# SNES-Adapter-Board.net
KiCad netlist of a schematic drawn in EAGLE
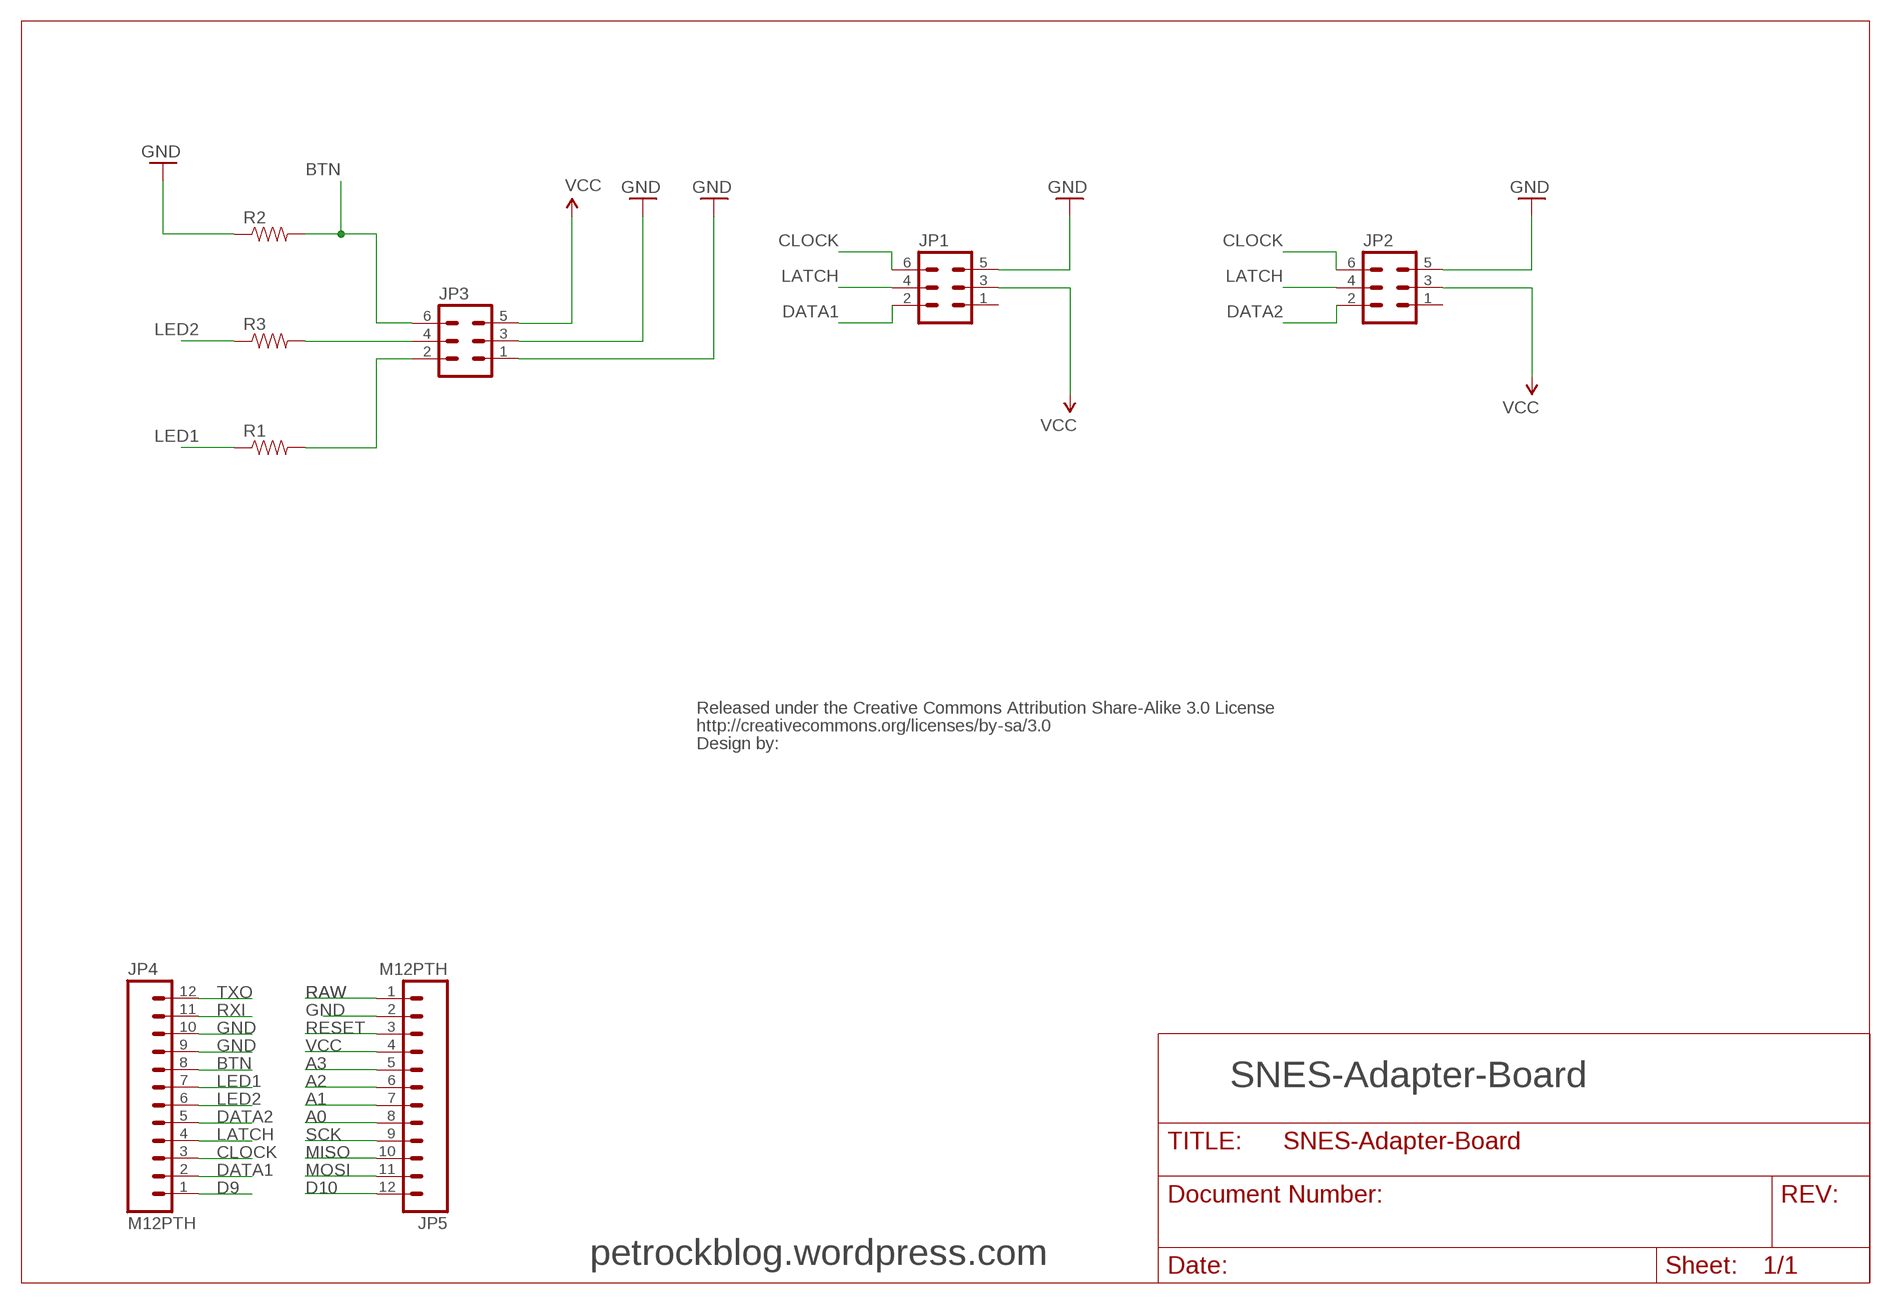
[diagram p0: schematic, sheet 1]

(export (version "E")
  (design (tool "Eeschema 10.0.6"))
  (components
    (comp (ref "JP1")
      (value "ML6")
      (footprint "eagle-import:ML6")
      (libsource (lib "eagle-import") (part "ML6"))
    )
    (comp (ref "JP2")
      (value "ML6")
      (footprint "eagle-import:ML6")
      (libsource (lib "eagle-import") (part "ML6"))
    )
    (comp (ref "JP3")
      (value "ML6")
      (footprint "eagle-import:ML6")
      (libsource (lib "eagle-import") (part "ML6"))
    )
    (comp (ref "JP4")
      (value "M12PTH")
      (footprint "eagle-import:1X12")
      (libsource (lib "eagle-import") (part "M12PTH"))
    )
    (comp (ref "JP5")
      (value "M12PTH")
      (footprint "eagle-import:1X12")
      (libsource (lib "eagle-import") (part "M12PTH"))
    )
    (comp (ref "R1")
      (value "RESISTORPTH-1/4W")
      (footprint "eagle-import:AXIAL-0.4")
      (libsource (lib "eagle-import") (part "RESISTORPTH-1/4W"))
    )
    (comp (ref "R2")
      (value "RESISTORPTH-1/4W")
      (footprint "eagle-import:AXIAL-0.4")
      (libsource (lib "eagle-import") (part "RESISTORPTH-1/4W"))
    )
    (comp (ref "R3")
      (value "RESISTORPTH-1/4W")
      (footprint "eagle-import:AXIAL-0.4")
      (libsource (lib "eagle-import") (part "RESISTORPTH-1/4W"))
    )
    (comp (ref "U$2")
      (value "CREATIVE_COMMONS")
      (footprint "eagle-import:CREATIVE_COMMONS")
      (libsource (lib "eagle-import") (part "CREATIVE_COMMONS"))
    )
  )
  (nets
    (net (code "1") (name "/A0") (class "Default")
      (node (ref "JP5") (pin "8") (pinfunction "8_8") (pintype "passive"))
    )
    (net (code "2") (name "/A1") (class "Default")
      (node (ref "JP5") (pin "7") (pinfunction "7_7") (pintype "passive"))
    )
    (net (code "3") (name "/A2") (class "Default")
      (node (ref "JP5") (pin "6") (pinfunction "6_6") (pintype "passive"))
    )
    (net (code "4") (name "/A3") (class "Default")
      (node (ref "JP5") (pin "5") (pinfunction "5_5") (pintype "passive"))
    )
    (net (code "5") (name "/BTN") (class "Default")
      (node (ref "JP3") (pin "6") (pinfunction "6_6") (pintype "passive"))
      (node (ref "JP4") (pin "8") (pinfunction "8_8") (pintype "passive"))
      (node (ref "R2") (pin "P$2") (pinfunction "2_P$2") (pintype "passive"))
    )
    (net (code "6") (name "/CLOCK") (class "Default")
      (node (ref "JP1") (pin "6") (pinfunction "6_6") (pintype "passive"))
      (node (ref "JP2") (pin "6") (pinfunction "6_6") (pintype "passive"))
      (node (ref "JP4") (pin "3") (pinfunction "3_3") (pintype "passive"))
    )
    (net (code "7") (name "/D9") (class "Default")
      (node (ref "JP4") (pin "1") (pinfunction "1_1") (pintype "passive"))
    )
    (net (code "8") (name "/D10") (class "Default")
      (node (ref "JP5") (pin "12") (pinfunction "12_12") (pintype "passive"))
    )
    (net (code "9") (name "/DATA1") (class "Default")
      (node (ref "JP1") (pin "2") (pinfunction "2_2") (pintype "passive"))
      (node (ref "JP4") (pin "2") (pinfunction "2_2") (pintype "passive"))
    )
    (net (code "10") (name "/DATA2") (class "Default")
      (node (ref "JP2") (pin "2") (pinfunction "2_2") (pintype "passive"))
      (node (ref "JP4") (pin "5") (pinfunction "5_5") (pintype "passive"))
    )
    (net (code "11") (name "/LATCH") (class "Default")
      (node (ref "JP1") (pin "4") (pinfunction "4_4") (pintype "passive"))
      (node (ref "JP2") (pin "4") (pinfunction "4_4") (pintype "passive"))
      (node (ref "JP4") (pin "4") (pinfunction "4_4") (pintype "passive"))
    )
    (net (code "12") (name "/LED1") (class "Default")
      (node (ref "JP4") (pin "7") (pinfunction "7_7") (pintype "passive"))
      (node (ref "R1") (pin "P$1") (pinfunction "1_P$1") (pintype "passive"))
    )
    (net (code "13") (name "/LED2") (class "Default")
      (node (ref "JP4") (pin "6") (pinfunction "6_6") (pintype "passive"))
      (node (ref "R3") (pin "P$1") (pinfunction "1_P$1") (pintype "passive"))
    )
    (net (code "14") (name "/MISO") (class "Default")
      (node (ref "JP5") (pin "10") (pinfunction "10_10") (pintype "passive"))
    )
    (net (code "15") (name "/MOSI") (class "Default")
      (node (ref "JP5") (pin "11") (pinfunction "11_11") (pintype "passive"))
    )
    (net (code "16") (name "/RAW") (class "Default")
      (node (ref "JP5") (pin "1") (pinfunction "1_1") (pintype "passive"))
    )
    (net (code "17") (name "/RESET") (class "Default")
      (node (ref "JP5") (pin "3") (pinfunction "3_3") (pintype "passive"))
    )
    (net (code "18") (name "/RXI") (class "Default")
      (node (ref "JP4") (pin "11") (pinfunction "11_11") (pintype "passive"))
    )
    (net (code "19") (name "/SCK") (class "Default")
      (node (ref "JP5") (pin "9") (pinfunction "9_9") (pintype "passive"))
    )
    (net (code "20") (name "/TXO") (class "Default")
      (node (ref "JP4") (pin "12") (pinfunction "12_12") (pintype "passive"))
    )
    (net (code "21") (name "GND") (class "Default")
      (node (ref "JP1") (pin "5") (pinfunction "5_5") (pintype "passive"))
      (node (ref "JP2") (pin "5") (pinfunction "5_5") (pintype "passive"))
      (node (ref "JP3") (pin "1") (pinfunction "1_1") (pintype "passive"))
      (node (ref "JP3") (pin "3") (pinfunction "3_3") (pintype "passive"))
      (node (ref "JP4") (pin "10") (pinfunction "10_10") (pintype "passive"))
      (node (ref "JP4") (pin "9") (pinfunction "9_9") (pintype "passive"))
      (node (ref "JP5") (pin "2") (pinfunction "2_2") (pintype "passive"))
      (node (ref "R2") (pin "P$1") (pinfunction "1_P$1") (pintype "passive"))
    )
    (net (code "22") (name "Net-(R1-2)") (class "Default")
      (node (ref "JP3") (pin "2") (pinfunction "2_2") (pintype "passive"))
      (node (ref "R1") (pin "P$2") (pinfunction "2_P$2") (pintype "passive"))
    )
    (net (code "23") (name "Net-(R3-2)") (class "Default")
      (node (ref "JP3") (pin "4") (pinfunction "4_4") (pintype "passive"))
      (node (ref "R3") (pin "P$2") (pinfunction "2_P$2") (pintype "passive"))
    )
    (net (code "24") (name "VCC") (class "Default")
      (node (ref "JP1") (pin "3") (pinfunction "3_3") (pintype "passive"))
      (node (ref "JP2") (pin "3") (pinfunction "3_3") (pintype "passive"))
      (node (ref "JP3") (pin "5") (pinfunction "5_5") (pintype "passive"))
      (node (ref "JP5") (pin "4") (pinfunction "4_4") (pintype "passive"))
    )
    (net (code "25") (name "unconnected-(JP1-Pad1)") (class "Default")
      (node (ref "JP1") (pin "1") (pinfunction "1_1") (pintype "passive"))
    )
    (net (code "26") (name "unconnected-(JP2-Pad1)") (class "Default")
      (node (ref "JP2") (pin "1") (pinfunction "1_1") (pintype "passive"))
    )
  )
)
